# Sheet1.net
KiCad netlist of a schematic drawn in Altium Designer
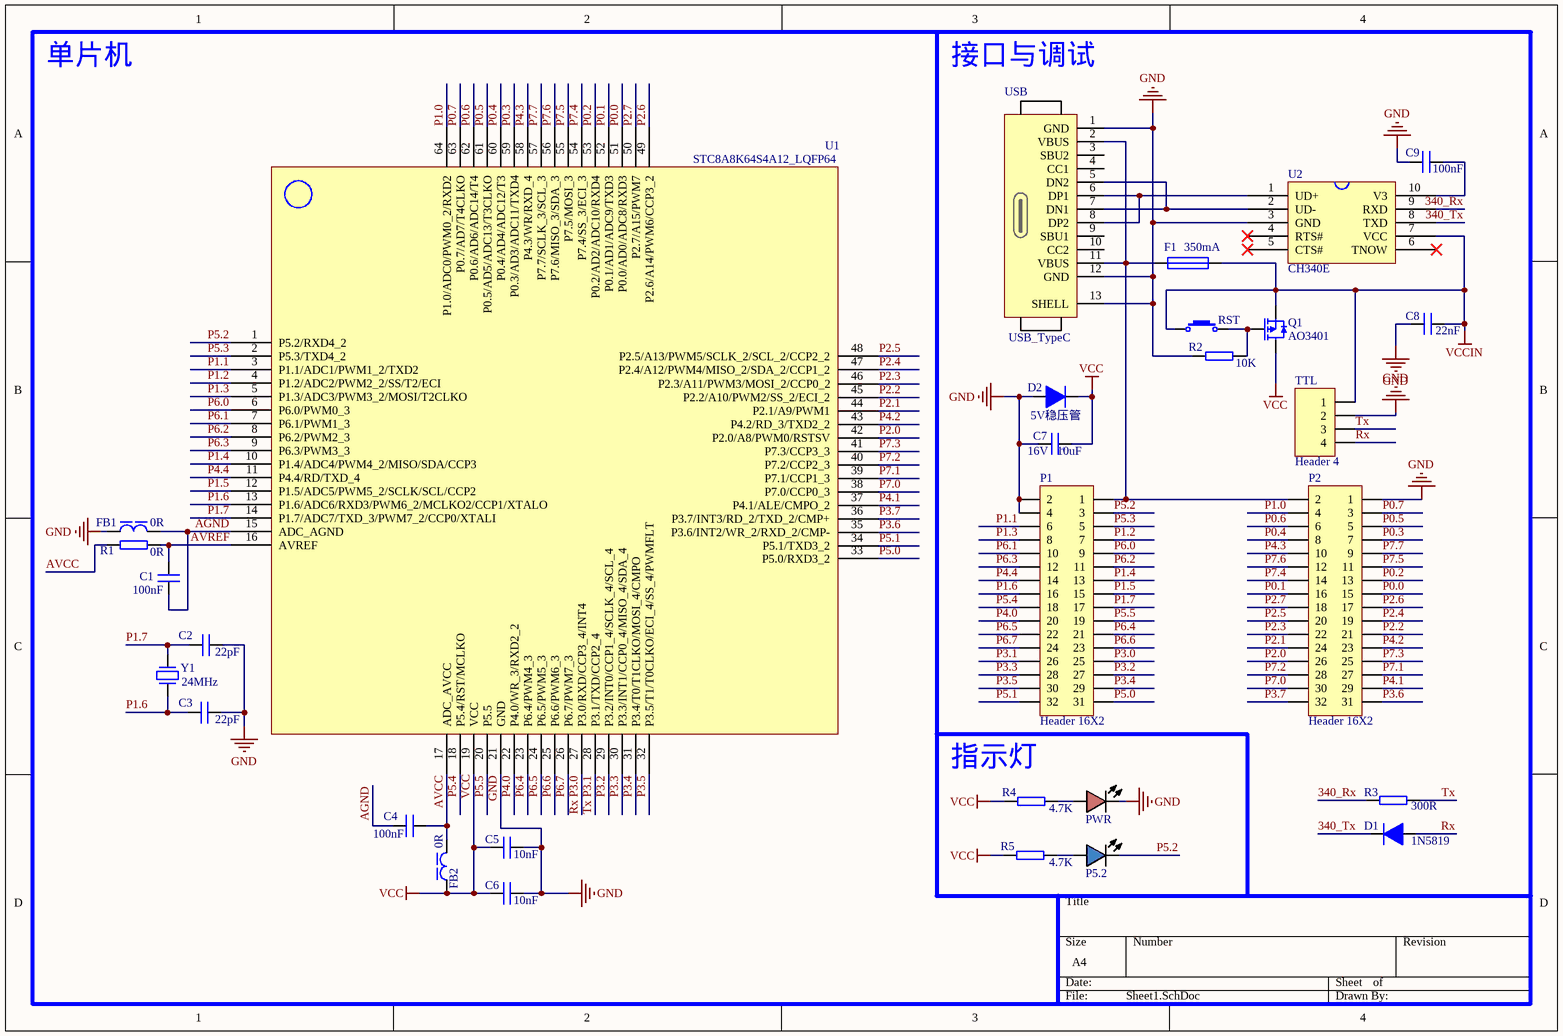
[diagram p0: Sheet1.SchDoc]

(export (version "E")
  (design (tool "Eeschema 10.0.6"))
  (components
    (comp (ref "C1")
      (value "100nF")
      (footprint "0603电容")
      (description "电容")
      (fields (field (name "版权归属") "源创客"))
      (libsource (lib "Schlib1") (part "Capacitor"))
    )
    (comp (ref "C2")
      (value "22pF")
      (footprint "0603电容")
      (description "电容")
      (fields (field (name "版权归属") "源创客"))
      (libsource (lib "Schlib1") (part "Capacitor"))
    )
    (comp (ref "C3")
      (value "22pF")
      (footprint "0603电容")
      (description "电容")
      (fields (field (name "版权归属") "源创客"))
      (libsource (lib "Schlib1") (part "Capacitor"))
    )
    (comp (ref "C4")
      (value "100nF")
      (footprint "0603电容")
      (description "电容")
      (fields (field (name "版权归属") "源创客"))
      (libsource (lib "Schlib1") (part "Capacitor"))
    )
    (comp (ref "C5")
      (value "10nF")
      (footprint "0603电容")
      (description "电容")
      (fields (field (name "版权归属") "源创客"))
      (libsource (lib "Schlib1") (part "Capacitor"))
    )
    (comp (ref "C6")
      (value "10nF")
      (footprint "0603电容")
      (description "电容")
      (fields (field (name "版权归属") "源创客"))
      (libsource (lib "Schlib1") (part "Capacitor"))
    )
    (comp (ref "C7")
      (value "16V   10uF")
      (footprint "Tan1206")
      (description "贴片钽电容")
      (fields (field (name "版权归属") "源创客"))
      (libsource (lib "Schlib1") (part "T_Capacitor"))
    )
    (comp (ref "C8")
      (value "22nF")
      (footprint "0603电容")
      (description "电容")
      (fields (field (name "版权归属") "源创客"))
      (libsource (lib "Schlib1") (part "Capacitor"))
    )
    (comp (ref "C9")
      (value "100nF")
      (footprint "0603电容")
      (description "电容")
      (fields (field (name "版权归属") "源创客"))
      (libsource (lib "Schlib1") (part "Capacitor"))
    )
    (comp (ref "D1") (value "1N5819") (footprint "SOD-323") (libsource (lib "Schlib1") (part "1N5819")))
    (comp (ref "D2") (value "5V稳压管") (footprint "SOD-323") (libsource (lib "Schlib1") (part "5V稳压管")))
    (comp (ref "F1")
      (value "350mA")
      (footprint "0603保险丝")
      (description "Fuse")
      (libsource (lib "Schlib1") (part "Fuse"))
    )
    (comp (ref "FB1")
      (value "0R")
      (footprint "0603磁珠")
      (description "磁珠")
      (libsource (lib "Schlib1") (part "FERRITE_BEAD"))
    )
    (comp (ref "FB2")
      (value "0R")
      (footprint "0603磁珠")
      (description "磁珠")
      (libsource (lib "Schlib1") (part "FERRITE_BEAD"))
    )
    (comp (ref "P1")
      (value "Header 16X2")
      (footprint "HDR-16X2")
      (description "16*2P接插件")
      (fields (field (name "版权归属") "源创客"))
      (libsource (lib "Schlib1") (part "Header 16X2"))
    )
    (comp (ref "P2")
      (value "Header 16X2")
      (footprint "HDR-16X2")
      (description "16*2P接插件")
      (fields (field (name "版权归属") "源创客"))
      (libsource (lib "Schlib1") (part "Header 16X2"))
    )
    (comp (ref "P5.2")
      (value "Blue_LED")
      (footprint "LED 0603B")
      (libsource (lib "Schlib1") (part "Blue_LED"))
    )
    (comp (ref "PWR") (value "Red_LED") (footprint "LED 0603R") (libsource (lib "Schlib1") (part "Red_LED")))
    (comp (ref "Q1")
      (value "AO3401")
      (footprint "SOT-23")
      (fields (field (name "版权归属") "源创客"))
      (libsource (lib "Schlib1") (part "AO3401"))
    )
    (comp (ref "R1")
      (value "0R")
      (footprint "0603电阻")
      (description "电阻")
      (fields (field (name "版权归属") "源创客"))
      (libsource (lib "Schlib1") (part "Resistor"))
    )
    (comp (ref "R2")
      (value "10K")
      (footprint "0603电阻")
      (description "电阻")
      (fields (field (name "版权归属") "源创客"))
      (libsource (lib "Schlib1") (part "Resistor"))
    )
    (comp (ref "R3")
      (value "300R")
      (footprint "0603电阻")
      (description "电阻")
      (fields (field (name "版权归属") "源创客"))
      (libsource (lib "Schlib1") (part "Resistor"))
    )
    (comp (ref "R4")
      (value "4.7K")
      (footprint "0603电阻")
      (description "电阻")
      (fields (field (name "版权归属") "源创客"))
      (libsource (lib "Schlib1") (part "Resistor"))
    )
    (comp (ref "R5")
      (value "4.7K")
      (footprint "0603电阻")
      (description "电阻")
      (fields (field (name "版权归属") "源创客"))
      (libsource (lib "Schlib1") (part "Resistor"))
    )
    (comp (ref "RST")
      (value "*")
      (footprint "SWD")
      (description "轻触开关")
      (libsource (lib "Schlib1") (part "SW_TB"))
    )
    (comp (ref "TTL")
      (value "Header 4")
      (footprint "HDR-1X4")
      (description "4P接插件")
      (fields (field (name "版权归属") "源创客"))
      (libsource (lib "Schlib1") (part "Header 4"))
    )
    (comp (ref "U1")
      (value "STC8A8K64S4A12_LQFP64")
      (footprint "LQFP64-10*10")
      (libsource (lib "Schlib1") (part "STC8A8K64S4A12_LQFP64"))
    )
    (comp (ref "U2") (value "CH340E") (footprint "MSOP-10") (libsource (lib "Schlib1") (part "CH340E")))
    (comp (ref "USB")
      (value "USB_TypeC")
      (footprint "USB3.1")
      (description "TypeC接口")
      (libsource (lib "Schlib1") (part "USB3.1"))
    )
    (comp (ref "Y1")
      (value "24MHz")
      (footprint "XTAL-SMD3225")
      (description "晶振")
      (fields (field (name "版权归属") "源创客"))
      (libsource (lib "Schlib1") (part "Crystal"))
    )
  )
  (nets
    (net (code "1") (name "/340_Rx") (class "Default")
      (node (ref "R3") (pin "1") (pinfunction "1_1") (pintype "passive"))
      (node (ref "U2") (pin "9") (pinfunction "RXD_9") (pintype "power_in"))
    )
    (net (code "2") (name "/340_Tx") (class "Default")
      (node (ref "D1") (pin "1") (pinfunction "1_1") (pintype "passive"))
      (node (ref "U2") (pin "8") (pinfunction "TXD_8") (pintype "power_in"))
    )
    (net (code "3") (name "/AGND") (class "Default")
      (node (ref "C1") (pin "2") (pinfunction "2_2") (pintype "passive"))
      (node (ref "C4") (pin "1") (pinfunction "1_1") (pintype "passive"))
      (node (ref "FB1") (pin "2") (pinfunction "2_2") (pintype "passive"))
      (node (ref "U1") (pin "15") (pinfunction "ADC_AGND_15") (pintype "passive"))
    )
    (net (code "4") (name "/AVCC") (class "Default")
      (node (ref "C4") (pin "2") (pinfunction "2_2") (pintype "passive"))
      (node (ref "FB2") (pin "2") (pinfunction "2_2") (pintype "passive"))
      (node (ref "R1") (pin "1") (pinfunction "1_1") (pintype "passive"))
      (node (ref "U1") (pin "17") (pinfunction "ADC_AVCC_17") (pintype "passive"))
    )
    (net (code "5") (name "/AVREF") (class "Default")
      (node (ref "C1") (pin "1") (pinfunction "1_1") (pintype "passive"))
      (node (ref "R1") (pin "2") (pinfunction "2_2") (pintype "passive"))
      (node (ref "U1") (pin "16") (pinfunction "AVREF_16") (pintype "passive"))
    )
    (net (code "6") (name "/P0.0") (class "Default")
      (node (ref "P2") (pin "15") (pinfunction "15_15") (pintype "passive"))
      (node (ref "U1") (pin "51") (pinfunction "P0.0/AD0/ADC8/RXD3_51") (pintype "passive"))
    )
    (net (code "7") (name "/P0.1") (class "Default")
      (node (ref "P2") (pin "16") (pinfunction "16_16") (pintype "passive"))
      (node (ref "U1") (pin "52") (pinfunction "P0.1/AD1/ADC9/TXD3_52") (pintype "passive"))
    )
    (net (code "8") (name "/P0.2") (class "Default")
      (node (ref "P2") (pin "13") (pinfunction "13_13") (pintype "passive"))
      (node (ref "U1") (pin "53") (pinfunction "P0.2/AD2/ADC10/RXD4_53") (pintype "passive"))
    )
    (net (code "9") (name "/P0.3") (class "Default")
      (node (ref "P2") (pin "7") (pinfunction "7_7") (pintype "passive"))
      (node (ref "U1") (pin "59") (pinfunction "P0.3/AD3/ADC11/TXD4_59") (pintype "passive"))
    )
    (net (code "10") (name "/P0.4") (class "Default")
      (node (ref "P2") (pin "8") (pinfunction "8_8") (pintype "passive"))
      (node (ref "U1") (pin "60") (pinfunction "P0.4/AD4/ADC12/T3_60") (pintype "passive"))
    )
    (net (code "11") (name "/P0.5") (class "Default")
      (node (ref "P2") (pin "5") (pinfunction "5_5") (pintype "passive"))
      (node (ref "U1") (pin "61") (pinfunction "P0.5/AD5/ADC13/T3CLKO_61") (pintype "passive"))
    )
    (net (code "12") (name "/P0.6") (class "Default")
      (node (ref "P2") (pin "6") (pinfunction "6_6") (pintype "passive"))
      (node (ref "U1") (pin "62") (pinfunction "P0.6/AD6/ADC14/T4_62") (pintype "passive"))
    )
    (net (code "13") (name "/P0.7") (class "Default")
      (node (ref "P2") (pin "3") (pinfunction "3_3") (pintype "passive"))
      (node (ref "U1") (pin "63") (pinfunction "P0.7/AD7/T4CLKO_63") (pintype "passive"))
    )
    (net (code "14") (name "/P1.0") (class "Default")
      (node (ref "P2") (pin "4") (pinfunction "4_4") (pintype "passive"))
      (node (ref "U1") (pin "64") (pinfunction "P1.0/ADC0/PWM0_2/RXD2_64") (pintype "passive"))
    )
    (net (code "15") (name "/P1.1") (class "Default")
      (node (ref "P1") (pin "6") (pinfunction "6_6") (pintype "passive"))
      (node (ref "U1") (pin "3") (pinfunction "P1.1/ADC1/PWM1_2/TXD2_3") (pintype "passive"))
    )
    (net (code "16") (name "/P1.2") (class "Default")
      (node (ref "P1") (pin "7") (pinfunction "7_7") (pintype "passive"))
      (node (ref "U1") (pin "4") (pinfunction "P1.2/ADC2/PWM2_2/SS/T2/ECI_4") (pintype "passive"))
    )
    (net (code "17") (name "/P1.3") (class "Default")
      (node (ref "P1") (pin "8") (pinfunction "8_8") (pintype "passive"))
      (node (ref "U1") (pin "5") (pinfunction "P1.3/ADC3/PWM3_2/MOSI/T2CLKO_5") (pintype "passive"))
    )
    (net (code "18") (name "/P1.4") (class "Default")
      (node (ref "P1") (pin "13") (pinfunction "13_13") (pintype "passive"))
      (node (ref "U1") (pin "10") (pinfunction "P1.4/ADC4/PWM4_2/MISO/SDA/CCP3_10") (pintype "passive"))
    )
    (net (code "19") (name "/P1.5") (class "Default")
      (node (ref "P1") (pin "15") (pinfunction "15_15") (pintype "passive"))
      (node (ref "U1") (pin "12") (pinfunction "P1.5/ADC5/PWM5_2/SCLK/SCL/CCP2_12") (pintype "passive"))
    )
    (net (code "20") (name "/P1.6") (class "Default")
      (node (ref "C3") (pin "1") (pinfunction "1_1") (pintype "passive"))
      (node (ref "P1") (pin "16") (pinfunction "16_16") (pintype "passive"))
      (node (ref "U1") (pin "13") (pinfunction "P1.6/ADC6/RXD3/PWM6_2/MCLKO2/CCP1/XTALO_13") (pintype "passive"))
      (node (ref "Y1") (pin "1") (pinfunction "1_1") (pintype "passive"))
    )
    (net (code "21") (name "/P1.7") (class "Default")
      (node (ref "C2") (pin "1") (pinfunction "1_1") (pintype "passive"))
      (node (ref "P1") (pin "17") (pinfunction "17_17") (pintype "passive"))
      (node (ref "U1") (pin "14") (pinfunction "P1.7/ADC7/TXD_3/PWM7_2/CCP0/XTALI_14") (pintype "passive"))
      (node (ref "Y1") (pin "3") (pinfunction "3_3") (pintype "passive"))
    )
    (net (code "22") (name "/P2.0") (class "Default")
      (node (ref "P2") (pin "26") (pinfunction "26_26") (pintype "passive"))
      (node (ref "U1") (pin "42") (pinfunction "P2.0/A8/PWM0/RSTSV_42") (pintype "passive"))
    )
    (net (code "23") (name "/P2.1") (class "Default")
      (node (ref "P2") (pin "24") (pinfunction "24_24") (pintype "passive"))
      (node (ref "U1") (pin "44") (pinfunction "P2.1/A9/PWM1_44") (pintype "passive"))
    )
    (net (code "24") (name "/P2.2") (class "Default")
      (node (ref "P2") (pin "21") (pinfunction "21_21") (pintype "passive"))
      (node (ref "U1") (pin "45") (pinfunction "P2.2/A10/PWM2/SS_2/ECI_2_45") (pintype "passive"))
    )
    (net (code "25") (name "/P2.3") (class "Default")
      (node (ref "P2") (pin "22") (pinfunction "22_22") (pintype "passive"))
      (node (ref "U1") (pin "46") (pinfunction "P2.3/A11/PWM3/MOSI_2/CCP0_2_46") (pintype "passive"))
    )
    (net (code "26") (name "/P2.4") (class "Default")
      (node (ref "P2") (pin "19") (pinfunction "19_19") (pintype "passive"))
      (node (ref "U1") (pin "47") (pinfunction "P2.4/A12/PWM4/MISO_2/SDA_2/CCP1_2_47") (pintype "passive"))
    )
    (net (code "27") (name "/P2.5") (class "Default")
      (node (ref "P2") (pin "20") (pinfunction "20_20") (pintype "passive"))
      (node (ref "U1") (pin "48") (pinfunction "P2.5/A13/PWM5/SCLK_2/SCL_2/CCP2_2_48") (pintype "passive"))
    )
    (net (code "28") (name "/P2.6") (class "Default")
      (node (ref "P2") (pin "17") (pinfunction "17_17") (pintype "passive"))
      (node (ref "U1") (pin "49") (pinfunction "P2.6/A14/PWM6/CCP3_2_49") (pintype "passive"))
    )
    (net (code "29") (name "/P2.7") (class "Default")
      (node (ref "P2") (pin "18") (pinfunction "18_18") (pintype "passive"))
      (node (ref "U1") (pin "50") (pinfunction "P2.7/A15/PWM7_50") (pintype "passive"))
    )
    (net (code "30") (name "/P3.0") (class "Default")
      (node (ref "D1") (pin "2") (pinfunction "2_2") (pintype "passive"))
      (node (ref "P1") (pin "25") (pinfunction "25_25") (pintype "passive"))
      (node (ref "TTL") (pin "4") (pinfunction "4_4") (pintype "passive"))
      (node (ref "U1") (pin "27") (pinfunction "P3.0/RXD/CCP3_4/INT4_27") (pintype "passive"))
    )
    (net (code "31") (name "/P3.1") (class "Default")
      (node (ref "P1") (pin "26") (pinfunction "26_26") (pintype "passive"))
      (node (ref "R3") (pin "2") (pinfunction "2_2") (pintype "passive"))
      (node (ref "TTL") (pin "3") (pinfunction "3_3") (pintype "passive"))
      (node (ref "U1") (pin "28") (pinfunction "P3.1/TXD/CCP2_4_28") (pintype "passive"))
    )
    (net (code "32") (name "/P3.2") (class "Default")
      (node (ref "P1") (pin "27") (pinfunction "27_27") (pintype "passive"))
      (node (ref "U1") (pin "29") (pinfunction "P3.2/INT0/CCP1_4/SCLK_4/SCL_4_29") (pintype "passive"))
    )
    (net (code "33") (name "/P3.3") (class "Default")
      (node (ref "P1") (pin "28") (pinfunction "28_28") (pintype "passive"))
      (node (ref "U1") (pin "30") (pinfunction "P3.3/INT1/CCP0_4/MISO_4/SDA_4_30") (pintype "passive"))
    )
    (net (code "34") (name "/P3.4") (class "Default")
      (node (ref "P1") (pin "29") (pinfunction "29_29") (pintype "passive"))
      (node (ref "U1") (pin "31") (pinfunction "P3.4/T0/T1CLKO/MOSI_4/CMPO_31") (pintype "passive"))
    )
    (net (code "35") (name "/P3.5") (class "Default")
      (node (ref "P1") (pin "30") (pinfunction "30_30") (pintype "passive"))
      (node (ref "U1") (pin "32") (pinfunction "P3.5/T1/T0CLKO/ECI_4/SS_4/PWMFLT_32") (pintype "passive"))
    )
    (net (code "36") (name "/P3.6") (class "Default")
      (node (ref "P2") (pin "31") (pinfunction "31_31") (pintype "passive"))
      (node (ref "U1") (pin "35") (pinfunction "P3.6/INT2/WR_2/RXD_2/CMP-_35") (pintype "passive"))
    )
    (net (code "37") (name "/P3.7") (class "Default")
      (node (ref "P2") (pin "32") (pinfunction "32_32") (pintype "passive"))
      (node (ref "U1") (pin "36") (pinfunction "P3.7/INT3/RD_2/TXD_2/CMP+_36") (pintype "passive"))
    )
    (net (code "38") (name "/P4.0") (class "Default")
      (node (ref "P1") (pin "20") (pinfunction "20_20") (pintype "passive"))
      (node (ref "U1") (pin "22") (pinfunction "P4.0/WR_3/RXD2_2_22") (pintype "passive"))
    )
    (net (code "39") (name "/P4.1") (class "Default")
      (node (ref "P2") (pin "29") (pinfunction "29_29") (pintype "passive"))
      (node (ref "U1") (pin "37") (pinfunction "P4.1/ALE/CMPO_2_37") (pintype "passive"))
    )
    (net (code "40") (name "/P4.2") (class "Default")
      (node (ref "P2") (pin "23") (pinfunction "23_23") (pintype "passive"))
      (node (ref "U1") (pin "43") (pinfunction "P4.2/RD_3/TXD2_2_43") (pintype "passive"))
    )
    (net (code "41") (name "/P4.3") (class "Default")
      (node (ref "P2") (pin "10") (pinfunction "10_10") (pintype "passive"))
      (node (ref "U1") (pin "58") (pinfunction "P4.3/WR/RXD_4_58") (pintype "passive"))
    )
    (net (code "42") (name "/P4.4") (class "Default")
      (node (ref "P1") (pin "14") (pinfunction "14_14") (pintype "passive"))
      (node (ref "U1") (pin "11") (pinfunction "P4.4/RD/TXD_4_11") (pintype "passive"))
    )
    (net (code "43") (name "/P5.0") (class "Default")
      (node (ref "P1") (pin "31") (pinfunction "31_31") (pintype "passive"))
      (node (ref "U1") (pin "33") (pinfunction "P5.0/RXD3_2_33") (pintype "passive"))
    )
    (net (code "44") (name "/P5.1") (class "Default")
      (node (ref "P1") (pin "32") (pinfunction "32_32") (pintype "passive"))
      (node (ref "U1") (pin "34") (pinfunction "P5.1/TXD3_2_34") (pintype "passive"))
    )
    (net (code "45") (name "/P5.2") (class "Default")
      (node (ref "P1") (pin "3") (pinfunction "3_3") (pintype "passive"))
      (node (ref "P5.2") (pin "2") (pinfunction "2_2") (pintype "passive"))
      (node (ref "U1") (pin "1") (pinfunction "P5.2/RXD4_2_1") (pintype "passive"))
    )
    (net (code "46") (name "/P5.3") (class "Default")
      (node (ref "P1") (pin "5") (pinfunction "5_5") (pintype "passive"))
      (node (ref "U1") (pin "2") (pinfunction "P5.3/TXD4_2_2") (pintype "passive"))
    )
    (net (code "47") (name "/P5.4") (class "Default")
      (node (ref "P1") (pin "18") (pinfunction "18_18") (pintype "passive"))
      (node (ref "U1") (pin "18") (pinfunction "P5.4/RST/MCLKO_18") (pintype "passive"))
    )
    (net (code "48") (name "/P5.5") (class "Default")
      (node (ref "P1") (pin "19") (pinfunction "19_19") (pintype "passive"))
      (node (ref "U1") (pin "20") (pinfunction "P5.5_20") (pintype "passive"))
    )
    (net (code "49") (name "/P6.0") (class "Default")
      (node (ref "P1") (pin "9") (pinfunction "9_9") (pintype "passive"))
      (node (ref "U1") (pin "6") (pinfunction "P6.0/PWM0_3_6") (pintype "passive"))
    )
    (net (code "50") (name "/P6.1") (class "Default")
      (node (ref "P1") (pin "10") (pinfunction "10_10") (pintype "passive"))
      (node (ref "U1") (pin "7") (pinfunction "P6.1/PWM1_3_7") (pintype "passive"))
    )
    (net (code "51") (name "/P6.2") (class "Default")
      (node (ref "P1") (pin "11") (pinfunction "11_11") (pintype "passive"))
      (node (ref "U1") (pin "8") (pinfunction "P6.2/PWM2_3_8") (pintype "passive"))
    )
    (net (code "52") (name "/P6.3") (class "Default")
      (node (ref "P1") (pin "12") (pinfunction "12_12") (pintype "passive"))
      (node (ref "U1") (pin "9") (pinfunction "P6.3/PWM3_3_9") (pintype "passive"))
    )
    (net (code "53") (name "/P6.4") (class "Default")
      (node (ref "P1") (pin "21") (pinfunction "21_21") (pintype "passive"))
      (node (ref "U1") (pin "23") (pinfunction "P6.4/PWM4_3_23") (pintype "passive"))
    )
    (net (code "54") (name "/P6.5") (class "Default")
      (node (ref "P1") (pin "22") (pinfunction "22_22") (pintype "passive"))
      (node (ref "U1") (pin "24") (pinfunction "P6.5/PWM5_3_24") (pintype "passive"))
    )
    (net (code "55") (name "/P6.6") (class "Default")
      (node (ref "P1") (pin "23") (pinfunction "23_23") (pintype "passive"))
      (node (ref "U1") (pin "25") (pinfunction "P6.6/PWM6_3_25") (pintype "passive"))
    )
    (net (code "56") (name "/P6.7") (class "Default")
      (node (ref "P1") (pin "24") (pinfunction "24_24") (pintype "passive"))
      (node (ref "U1") (pin "26") (pinfunction "P6.7/PWM7_3_26") (pintype "passive"))
    )
    (net (code "57") (name "/P7.0") (class "Default")
      (node (ref "P2") (pin "30") (pinfunction "30_30") (pintype "passive"))
      (node (ref "U1") (pin "38") (pinfunction "P7.0/CCP0_3_38") (pintype "passive"))
    )
    (net (code "58") (name "/P7.1") (class "Default")
      (node (ref "P2") (pin "27") (pinfunction "27_27") (pintype "passive"))
      (node (ref "U1") (pin "39") (pinfunction "P7.1/CCP1_3_39") (pintype "passive"))
    )
    (net (code "59") (name "/P7.2") (class "Default")
      (node (ref "P2") (pin "28") (pinfunction "28_28") (pintype "passive"))
      (node (ref "U1") (pin "40") (pinfunction "P7.2/CCP2_3_40") (pintype "passive"))
    )
    (net (code "60") (name "/P7.3") (class "Default")
      (node (ref "P2") (pin "25") (pinfunction "25_25") (pintype "passive"))
      (node (ref "U1") (pin "41") (pinfunction "P7.3/CCP3_3_41") (pintype "passive"))
    )
    (net (code "61") (name "/P7.4") (class "Default")
      (node (ref "P2") (pin "14") (pinfunction "14_14") (pintype "passive"))
      (node (ref "U1") (pin "54") (pinfunction "P7.4/SS_3/ECI_3_54") (pintype "passive"))
    )
    (net (code "62") (name "/P7.5") (class "Default")
      (node (ref "P2") (pin "11") (pinfunction "11_11") (pintype "passive"))
      (node (ref "U1") (pin "55") (pinfunction "P7.5/MOSI_3_55") (pintype "passive"))
    )
    (net (code "63") (name "/P7.6") (class "Default")
      (node (ref "P2") (pin "12") (pinfunction "12_12") (pintype "passive"))
      (node (ref "U1") (pin "56") (pinfunction "P7.6/MISO_3/SDA_3_56") (pintype "passive"))
    )
    (net (code "64") (name "/P7.7") (class "Default")
      (node (ref "P2") (pin "9") (pinfunction "9_9") (pintype "passive"))
      (node (ref "U1") (pin "57") (pinfunction "P7.7/SCLK_3/SCL_3_57") (pintype "passive"))
    )
    (net (code "65") (name "GND") (class "Default")
      (node (ref "C2") (pin "2") (pinfunction "2_2") (pintype "passive"))
      (node (ref "C3") (pin "2") (pinfunction "2_2") (pintype "passive"))
      (node (ref "C5") (pin "2") (pinfunction "2_2") (pintype "passive"))
      (node (ref "C6") (pin "2") (pinfunction "2_2") (pintype "passive"))
      (node (ref "C7") (pin "2") (pinfunction "K_2") (pintype "passive"))
      (node (ref "C8") (pin "1") (pinfunction "1_1") (pintype "passive"))
      (node (ref "C9") (pin "1") (pinfunction "1_1") (pintype "passive"))
      (node (ref "D2") (pin "2") (pinfunction "2_2") (pintype "passive"))
      (node (ref "FB1") (pin "1") (pinfunction "1_1") (pintype "passive"))
      (node (ref "P1") (pin "2") (pinfunction "2_2") (pintype "passive"))
      (node (ref "P1") (pin "4") (pinfunction "4_4") (pintype "passive"))
      (node (ref "P2") (pin "1") (pinfunction "1_1") (pintype "passive"))
      (node (ref "PWR") (pin "2") (pinfunction "2_2") (pintype "passive"))
      (node (ref "R2") (pin "1") (pinfunction "1_1") (pintype "passive"))
      (node (ref "TTL") (pin "2") (pinfunction "2_2") (pintype "passive"))
      (node (ref "U1") (pin "21") (pinfunction "GND_21") (pintype "passive"))
      (node (ref "U2") (pin "3") (pinfunction "GND_3") (pintype "passive"))
      (node (ref "USB") (pin "1") (pinfunction "GND_1") (pintype "passive"))
      (node (ref "USB") (pin "12") (pinfunction "GND_12") (pintype "passive"))
      (node (ref "USB") (pin "13") (pinfunction "SHELL_13") (pintype "passive"))
    )
    (net (code "66") (name "Net-(F1-Pad1)") (class "Default")
      (node (ref "F1") (pin "1") (pinfunction "1_1") (pintype "passive"))
      (node (ref "P1") (pin "1") (pinfunction "1_1") (pintype "passive"))
      (node (ref "P2") (pin "2") (pinfunction "2_2") (pintype "passive"))
      (node (ref "USB") (pin "11") (pinfunction "VBUS_11") (pintype "passive"))
      (node (ref "USB") (pin "2") (pinfunction "VBUS_2") (pintype "passive"))
    )
    (net (code "67") (name "Net-(P5.2-Pad1)") (class "Default")
      (node (ref "P5.2") (pin "1") (pinfunction "1_1") (pintype "passive"))
      (node (ref "R5") (pin "2") (pinfunction "2_2") (pintype "passive"))
    )
    (net (code "68") (name "Net-(PWR-Pad1)") (class "Default")
      (node (ref "PWR") (pin "1") (pinfunction "1_1") (pintype "passive"))
      (node (ref "R4") (pin "2") (pinfunction "2_2") (pintype "passive"))
    )
    (net (code "69") (name "Net-(Q1-Pad1)") (class "Default")
      (node (ref "Q1") (pin "1") (pinfunction "1_1") (pintype "passive"))
      (node (ref "R2") (pin "2") (pinfunction "2_2") (pintype "passive"))
      (node (ref "RST") (pin "2") (pinfunction "2_2") (pintype "passive"))
    )
    (net (code "70") (name "Net-(U2-UD+)") (class "Default")
      (node (ref "U2") (pin "1") (pinfunction "UD+_1") (pintype "passive"))
      (node (ref "USB") (pin "6") (pinfunction "DP1_6") (pintype "passive"))
      (node (ref "USB") (pin "8") (pinfunction "DP2_8") (pintype "passive"))
    )
    (net (code "71") (name "Net-(U2-UD-)") (class "Default")
      (node (ref "U2") (pin "2") (pinfunction "UD-_2") (pintype "passive"))
      (node (ref "USB") (pin "5") (pinfunction "DN2_5") (pintype "passive"))
      (node (ref "USB") (pin "7") (pinfunction "DN1_7") (pintype "passive"))
    )
    (net (code "72") (name "Net-(U2-V3)") (class "Default")
      (node (ref "C9") (pin "2") (pinfunction "2_2") (pintype "passive"))
      (node (ref "U2") (pin "10") (pinfunction "V3_10") (pintype "passive"))
    )
    (net (code "73") (name "VCC") (class "Default")
      (node (ref "C5") (pin "1") (pinfunction "1_1") (pintype "passive"))
      (node (ref "C6") (pin "1") (pinfunction "1_1") (pintype "passive"))
      (node (ref "C7") (pin "1") (pinfunction "A_1") (pintype "passive"))
      (node (ref "D2") (pin "1") (pinfunction "1_1") (pintype "passive"))
      (node (ref "FB2") (pin "1") (pinfunction "1_1") (pintype "passive"))
      (node (ref "Q1") (pin "2") (pinfunction "2_2") (pintype "passive"))
      (node (ref "R4") (pin "1") (pinfunction "1_1") (pintype "passive"))
      (node (ref "R5") (pin "1") (pinfunction "1_1") (pintype "passive"))
      (node (ref "U1") (pin "19") (pinfunction "VCC_19") (pintype "passive"))
    )
    (net (code "74") (name "VCCIN") (class "Default")
      (node (ref "C8") (pin "2") (pinfunction "2_2") (pintype "passive"))
      (node (ref "F1") (pin "2") (pinfunction "2_2") (pintype "passive"))
      (node (ref "Q1") (pin "3") (pinfunction "3_3") (pintype "passive"))
      (node (ref "RST") (pin "1") (pinfunction "1_1") (pintype "passive"))
      (node (ref "TTL") (pin "1") (pinfunction "1_1") (pintype "passive"))
      (node (ref "U2") (pin "7") (pinfunction "VCC_7") (pintype "passive"))
    )
    (net (code "75") (name "unconnected-(U2-CTS#-Pad5)") (class "Default")
      (node (ref "U2") (pin "5") (pinfunction "CTS#_5") (pintype "passive+no_connect"))
    )
    (net (code "76") (name "unconnected-(U2-RTS#-Pad4)") (class "Default")
      (node (ref "U2") (pin "4") (pinfunction "RTS#_4") (pintype "passive+no_connect"))
    )
    (net (code "77") (name "unconnected-(U2-TNOW-Pad6)") (class "Default")
      (node (ref "U2") (pin "6") (pinfunction "TNOW_6") (pintype "passive+no_connect"))
    )
    (net (code "78") (name "unconnected-(USB-CC1-Pad4)") (class "Default")
      (node (ref "USB") (pin "4") (pinfunction "CC1_4") (pintype "passive"))
    )
    (net (code "79") (name "unconnected-(USB-CC2-Pad10)") (class "Default")
      (node (ref "USB") (pin "10") (pinfunction "CC2_10") (pintype "passive"))
    )
    (net (code "80") (name "unconnected-(USB-SBU1-Pad9)") (class "Default")
      (node (ref "USB") (pin "9") (pinfunction "SBU1_9") (pintype "passive"))
    )
    (net (code "81") (name "unconnected-(USB-SBU2-Pad3)") (class "Default")
      (node (ref "USB") (pin "3") (pinfunction "SBU2_3") (pintype "passive"))
    )
  )
)
